# CraneCon.net
KiCad netlist of a schematic drawn in EAGLE
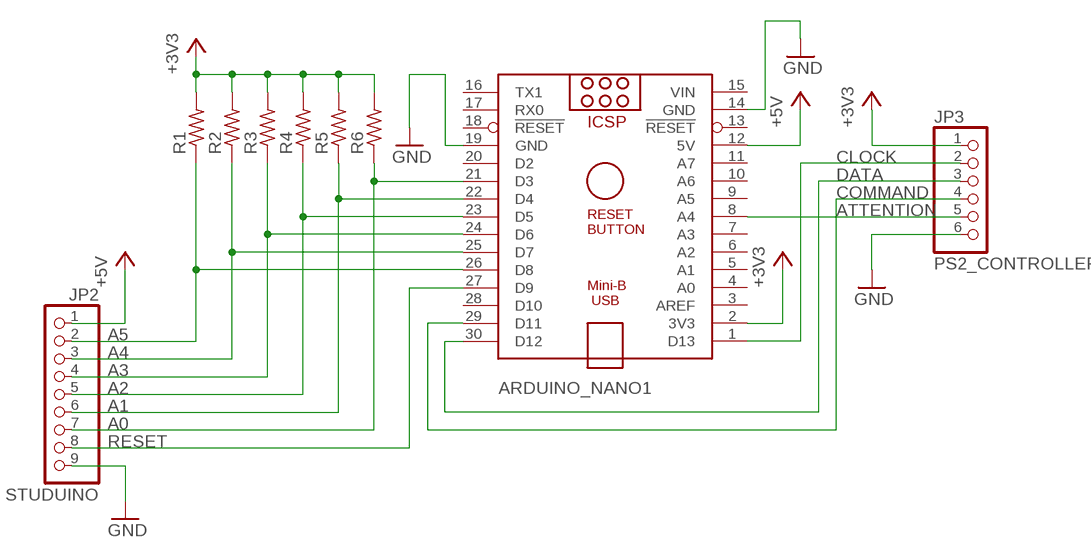
[diagram p0: schematic, sheet 1]

(export (version "E")
  (design (tool "Eeschema 10.0.6"))
  (components
    (comp (ref "ARDUINO_NANO1")
      (value "ARDUINO_NANO")
      (footprint "eagle-import:ARDUINO_NANO")
      (libsource (lib "eagle-import") (part "ARDUINO_NANO"))
    )
    (comp (ref "JP2")
      (value "STUDUINO")
      (footprint "eagle-import:1X09")
      (libsource (lib "eagle-import") (part "PINHD-1X9"))
    )
    (comp (ref "JP3")
      (value "PS2_CONTROLLER")
      (footprint "eagle-import:1X06")
      (libsource (lib "eagle-import") (part "PINHD-1X6"))
    )
    (comp (ref "R1")
      (value "R-US_0204/7")
      (footprint "eagle-import:0204_7")
      (libsource (lib "eagle-import") (part "R-US_0204/7"))
    )
    (comp (ref "R2")
      (value "R-US_0204/7")
      (footprint "eagle-import:0204_7")
      (libsource (lib "eagle-import") (part "R-US_0204/7"))
    )
    (comp (ref "R3")
      (value "R-US_0204/7")
      (footprint "eagle-import:0204_7")
      (libsource (lib "eagle-import") (part "R-US_0204/7"))
    )
    (comp (ref "R4")
      (value "R-US_0204/7")
      (footprint "eagle-import:0204_7")
      (libsource (lib "eagle-import") (part "R-US_0204/7"))
    )
    (comp (ref "R5")
      (value "R-US_0204/7")
      (footprint "eagle-import:0204_7")
      (libsource (lib "eagle-import") (part "R-US_0204/7"))
    )
    (comp (ref "R6")
      (value "R-US_0204/7")
      (footprint "eagle-import:0204_7")
      (libsource (lib "eagle-import") (part "R-US_0204/7"))
    )
  )
  (nets
    (net (code "1") (name "+3V3") (class "Default")
      (node (ref "ARDUINO_NANO1") (pin "2") (pinfunction "3V3_2") (pintype "output"))
      (node (ref "JP3") (pin "1") (pinfunction "1_1") (pintype "passive"))
      (node (ref "R1") (pin "2") (pinfunction "2_2") (pintype "passive"))
      (node (ref "R2") (pin "2") (pinfunction "2_2") (pintype "passive"))
      (node (ref "R3") (pin "2") (pinfunction "2_2") (pintype "passive"))
      (node (ref "R4") (pin "2") (pinfunction "2_2") (pintype "passive"))
      (node (ref "R5") (pin "2") (pinfunction "2_2") (pintype "passive"))
      (node (ref "R6") (pin "2") (pinfunction "2_2") (pintype "passive"))
    )
    (net (code "2") (name "+5V") (class "Default")
      (node (ref "ARDUINO_NANO1") (pin "12") (pinfunction "5V_12") (pintype "power_in"))
      (node (ref "JP2") (pin "1") (pinfunction "1_1") (pintype "passive"))
    )
    (net (code "3") (name "/A0") (class "Default")
      (node (ref "ARDUINO_NANO1") (pin "21") (pinfunction "D3_21") (pintype "bidirectional"))
      (node (ref "JP2") (pin "7") (pinfunction "7_7") (pintype "passive"))
      (node (ref "R6") (pin "1") (pinfunction "1_1") (pintype "passive"))
    )
    (net (code "4") (name "/A1") (class "Default")
      (node (ref "ARDUINO_NANO1") (pin "22") (pinfunction "D4_22") (pintype "bidirectional"))
      (node (ref "JP2") (pin "6") (pinfunction "6_6") (pintype "passive"))
      (node (ref "R5") (pin "1") (pinfunction "1_1") (pintype "passive"))
    )
    (net (code "5") (name "/A2") (class "Default")
      (node (ref "ARDUINO_NANO1") (pin "23") (pinfunction "D5_23") (pintype "bidirectional"))
      (node (ref "JP2") (pin "5") (pinfunction "5_5") (pintype "passive"))
      (node (ref "R4") (pin "1") (pinfunction "1_1") (pintype "passive"))
    )
    (net (code "6") (name "/A3") (class "Default")
      (node (ref "ARDUINO_NANO1") (pin "24") (pinfunction "D6_24") (pintype "bidirectional"))
      (node (ref "JP2") (pin "4") (pinfunction "4_4") (pintype "passive"))
      (node (ref "R3") (pin "1") (pinfunction "1_1") (pintype "passive"))
    )
    (net (code "7") (name "/A4") (class "Default")
      (node (ref "ARDUINO_NANO1") (pin "25") (pinfunction "D7_25") (pintype "bidirectional"))
      (node (ref "JP2") (pin "3") (pinfunction "3_3") (pintype "passive"))
      (node (ref "R2") (pin "1") (pinfunction "1_1") (pintype "passive"))
    )
    (net (code "8") (name "/A5") (class "Default")
      (node (ref "ARDUINO_NANO1") (pin "26") (pinfunction "D8_26") (pintype "bidirectional"))
      (node (ref "JP2") (pin "2") (pinfunction "2_2") (pintype "passive"))
      (node (ref "R1") (pin "1") (pinfunction "1_1") (pintype "passive"))
    )
    (net (code "9") (name "/ATTENTION") (class "Default")
      (node (ref "ARDUINO_NANO1") (pin "8") (pinfunction "A4_8") (pintype "bidirectional"))
      (node (ref "JP3") (pin "5") (pinfunction "5_5") (pintype "passive"))
    )
    (net (code "10") (name "/CLOCK") (class "Default")
      (node (ref "ARDUINO_NANO1") (pin "1") (pinfunction "D13_1") (pintype "bidirectional"))
      (node (ref "JP3") (pin "2") (pinfunction "2_2") (pintype "passive"))
    )
    (net (code "11") (name "/COMMAND") (class "Default")
      (node (ref "ARDUINO_NANO1") (pin "29") (pinfunction "D11_29") (pintype "bidirectional"))
      (node (ref "JP3") (pin "4") (pinfunction "4_4") (pintype "passive"))
    )
    (net (code "12") (name "/DATA") (class "Default")
      (node (ref "ARDUINO_NANO1") (pin "30") (pinfunction "D12_30") (pintype "bidirectional"))
      (node (ref "JP3") (pin "3") (pinfunction "3_3") (pintype "passive"))
    )
    (net (code "13") (name "/RESET") (class "Default")
      (node (ref "ARDUINO_NANO1") (pin "27") (pinfunction "D9_27") (pintype "bidirectional"))
      (node (ref "JP2") (pin "8") (pinfunction "8_8") (pintype "passive"))
    )
    (net (code "14") (name "/VIN") (class "Default")
      (node (ref "ARDUINO_NANO1") (pin "15") (pinfunction "VIN_15") (pintype "power_in"))
    )
    (net (code "15") (name "GND") (class "Default")
      (node (ref "ARDUINO_NANO1") (pin "14") (pinfunction "GND_14") (pintype "power_in"))
      (node (ref "ARDUINO_NANO1") (pin "19") (pinfunction "GND_19") (pintype "power_in"))
      (node (ref "JP2") (pin "9") (pinfunction "9_9") (pintype "passive"))
      (node (ref "JP3") (pin "6") (pinfunction "6_6") (pintype "passive"))
    )
    (net (code "16") (name "unconnected-(ARDUINO_NANO1-A0-Pad4)") (class "Default")
      (node (ref "ARDUINO_NANO1") (pin "4") (pinfunction "A0_4") (pintype "bidirectional"))
    )
    (net (code "17") (name "unconnected-(ARDUINO_NANO1-A1-Pad5)") (class "Default")
      (node (ref "ARDUINO_NANO1") (pin "5") (pinfunction "A1_5") (pintype "bidirectional"))
    )
    (net (code "18") (name "unconnected-(ARDUINO_NANO1-A2-Pad6)") (class "Default")
      (node (ref "ARDUINO_NANO1") (pin "6") (pinfunction "A2_6") (pintype "bidirectional"))
    )
    (net (code "19") (name "unconnected-(ARDUINO_NANO1-A3-Pad7)") (class "Default")
      (node (ref "ARDUINO_NANO1") (pin "7") (pinfunction "A3_7") (pintype "bidirectional"))
    )
    (net (code "20") (name "unconnected-(ARDUINO_NANO1-A5-Pad9)") (class "Default")
      (node (ref "ARDUINO_NANO1") (pin "9") (pinfunction "A5_9") (pintype "bidirectional"))
    )
    (net (code "21") (name "unconnected-(ARDUINO_NANO1-A6-Pad10)") (class "Default")
      (node (ref "ARDUINO_NANO1") (pin "10") (pinfunction "A6_10") (pintype "bidirectional"))
    )
    (net (code "22") (name "unconnected-(ARDUINO_NANO1-A7-Pad11)") (class "Default")
      (node (ref "ARDUINO_NANO1") (pin "11") (pinfunction "A7_11") (pintype "bidirectional"))
    )
    (net (code "23") (name "unconnected-(ARDUINO_NANO1-AREF-Pad3)") (class "Default")
      (node (ref "ARDUINO_NANO1") (pin "3") (pinfunction "AREF_3") (pintype "input"))
    )
    (net (code "24") (name "unconnected-(ARDUINO_NANO1-D2-Pad20)") (class "Default")
      (node (ref "ARDUINO_NANO1") (pin "20") (pinfunction "D2_20") (pintype "bidirectional"))
    )
    (net (code "25") (name "unconnected-(ARDUINO_NANO1-D10-Pad28)") (class "Default")
      (node (ref "ARDUINO_NANO1") (pin "28") (pinfunction "D10_28") (pintype "bidirectional"))
    )
    (net (code "26") (name "unconnected-(ARDUINO_NANO1-RX0-Pad17)") (class "Default")
      (node (ref "ARDUINO_NANO1") (pin "17") (pinfunction "RX0_17") (pintype "bidirectional"))
    )
    (net (code "27") (name "unconnected-(ARDUINO_NANO1-TX1-Pad16)") (class "Default")
      (node (ref "ARDUINO_NANO1") (pin "16") (pinfunction "TX1_16") (pintype "bidirectional"))
    )
    (net (code "28") (name "unconnected-(ARDUINO_NANO1-~{RESET}-Pad13)") (class "Default")
      (node (ref "ARDUINO_NANO1") (pin "13") (pinfunction "~{RESET}_13") (pintype "input"))
    )
    (net (code "29") (name "unconnected-(ARDUINO_NANO1-~{RESET}-Pad18)") (class "Default")
      (node (ref "ARDUINO_NANO1") (pin "18") (pinfunction "~{RESET}_18") (pintype "input"))
    )
  )
)
